# DJ_Controller_Circuit.net
KiCad netlist of a schematic drawn in EasyEDA Pro
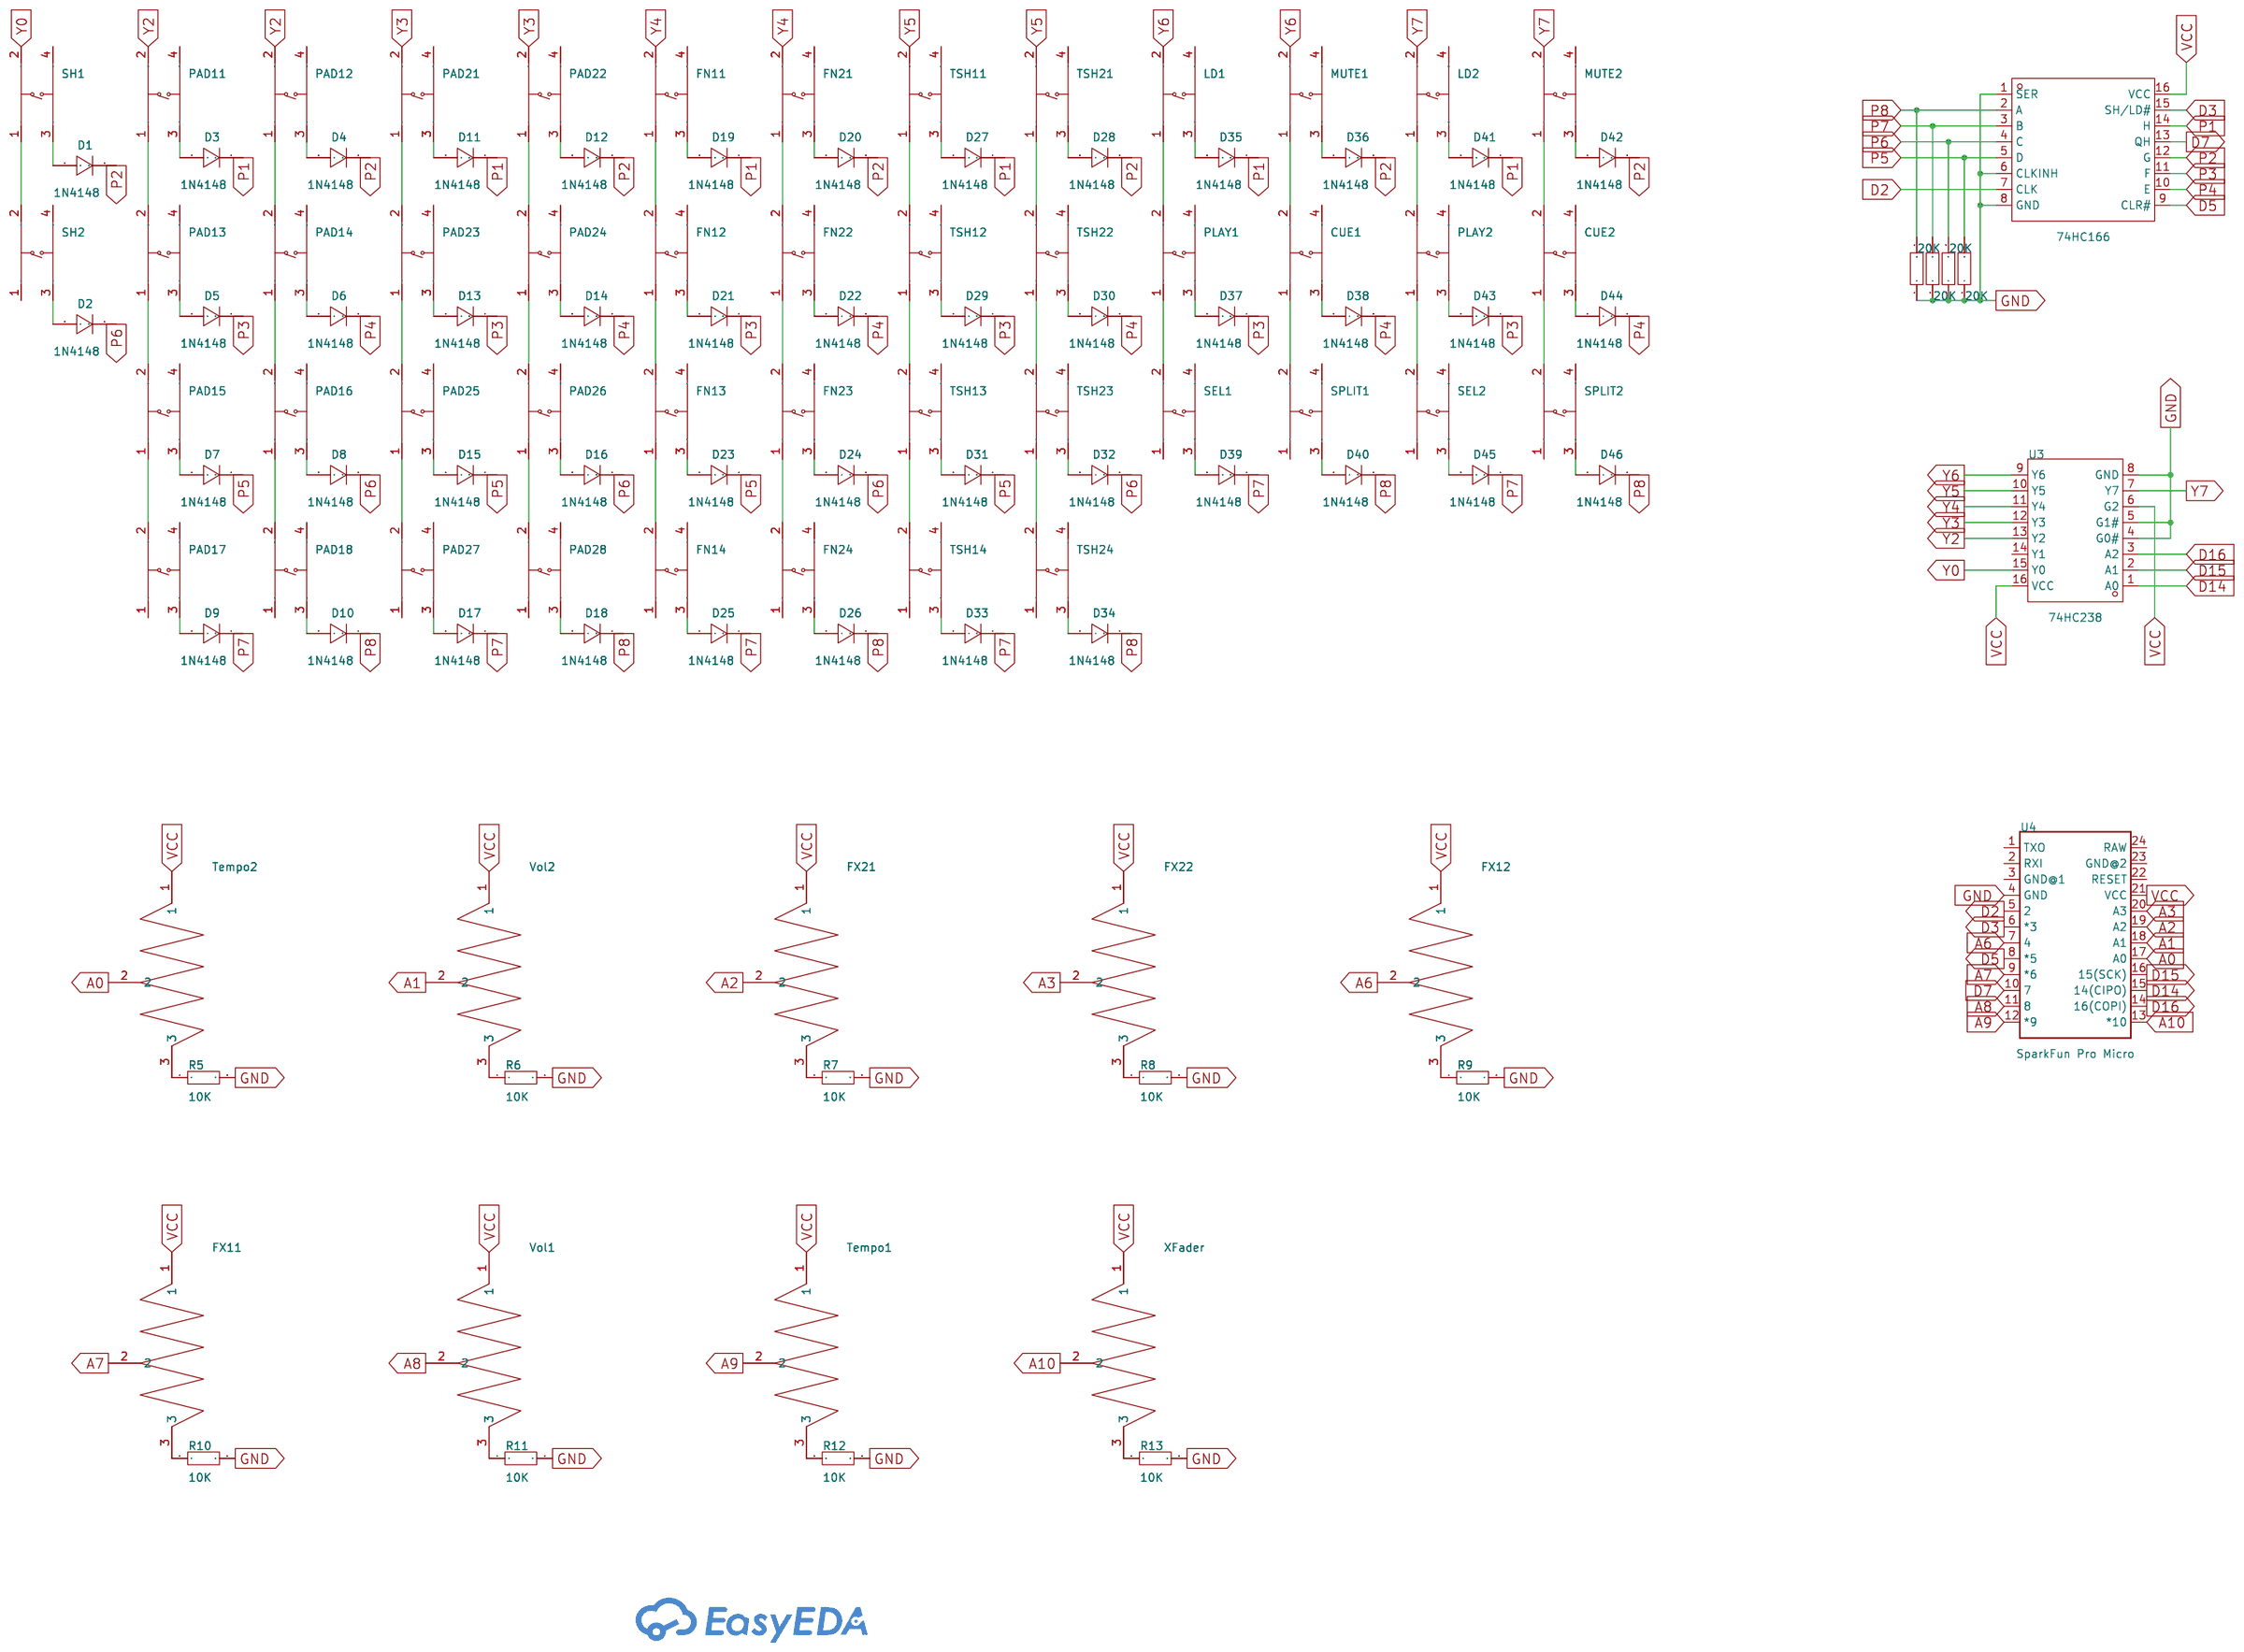
[diagram p0: schematic sheet]

(export (version "E")
  (design (tool "Eeschema 10.0.6"))
  (components
    (comp (ref "CUE1")
      (value "TS665CJ")
      (footprint "easyedapro:SW-TH_4P-L6.0-W6.0-P4.50-LS6.5")
      (fields (field (name "Manufacturer") "SHOU HAN(首韩)"))
      (libsource (lib "easyedapro") (part "TS665CJ"))
    )
    (comp (ref "CUE2")
      (value "TS665CJ")
      (footprint "easyedapro:SW-TH_4P-L6.0-W6.0-P4.50-LS6.5")
      (fields (field (name "Manufacturer") "SHOU HAN(首韩)"))
      (libsource (lib "easyedapro") (part "TS665CJ"))
    )
    (comp (ref "D1")
      (value "1N4148")
      (footprint "easyedapro:DO-35_BD2.0-L4.2-P8.20-D0.5-RD")
      (fields (field (name "Manufacturer") "星海"))
      (libsource (lib "easyedapro") (part "1N4148-C85057"))
    )
    (comp (ref "D2")
      (value "1N4148")
      (footprint "easyedapro:DO-35_BD2.0-L4.2-P8.20-D0.5-RD")
      (fields (field (name "Manufacturer") "星海"))
      (libsource (lib "easyedapro") (part "1N4148-C85057"))
    )
    (comp (ref "D3")
      (value "1N4148")
      (footprint "easyedapro:DO-35_BD2.0-L4.2-P8.20-D0.5-RD")
      (fields (field (name "Manufacturer") "星海"))
      (libsource (lib "easyedapro") (part "1N4148-C85057"))
    )
    (comp (ref "D4")
      (value "1N4148")
      (footprint "easyedapro:DO-35_BD2.0-L4.2-P8.20-D0.5-RD")
      (fields (field (name "Manufacturer") "星海"))
      (libsource (lib "easyedapro") (part "1N4148-C85057"))
    )
    (comp (ref "D5")
      (value "1N4148")
      (footprint "easyedapro:DO-35_BD2.0-L4.2-P8.20-D0.5-RD")
      (fields (field (name "Manufacturer") "星海"))
      (libsource (lib "easyedapro") (part "1N4148-C85057"))
    )
    (comp (ref "D6")
      (value "1N4148")
      (footprint "easyedapro:DO-35_BD2.0-L4.2-P8.20-D0.5-RD")
      (fields (field (name "Manufacturer") "星海"))
      (libsource (lib "easyedapro") (part "1N4148-C85057"))
    )
    (comp (ref "D7")
      (value "1N4148")
      (footprint "easyedapro:DO-35_BD2.0-L4.2-P8.20-D0.5-RD")
      (fields (field (name "Manufacturer") "星海"))
      (libsource (lib "easyedapro") (part "1N4148-C85057"))
    )
    (comp (ref "D8")
      (value "1N4148")
      (footprint "easyedapro:DO-35_BD2.0-L4.2-P8.20-D0.5-RD")
      (fields (field (name "Manufacturer") "星海"))
      (libsource (lib "easyedapro") (part "1N4148-C85057"))
    )
    (comp (ref "D9")
      (value "1N4148")
      (footprint "easyedapro:DO-35_BD2.0-L4.2-P8.20-D0.5-RD")
      (fields (field (name "Manufacturer") "星海"))
      (libsource (lib "easyedapro") (part "1N4148-C85057"))
    )
    (comp (ref "D10")
      (value "1N4148")
      (footprint "easyedapro:DO-35_BD2.0-L4.2-P8.20-D0.5-RD")
      (fields (field (name "Manufacturer") "星海"))
      (libsource (lib "easyedapro") (part "1N4148-C85057"))
    )
    (comp (ref "D11")
      (value "1N4148")
      (footprint "easyedapro:DO-35_BD2.0-L4.2-P8.20-D0.5-RD")
      (fields (field (name "Manufacturer") "星海"))
      (libsource (lib "easyedapro") (part "1N4148-C85057"))
    )
    (comp (ref "D12")
      (value "1N4148")
      (footprint "easyedapro:DO-35_BD2.0-L4.2-P8.20-D0.5-RD")
      (fields (field (name "Manufacturer") "星海"))
      (libsource (lib "easyedapro") (part "1N4148-C85057"))
    )
    (comp (ref "D13")
      (value "1N4148")
      (footprint "easyedapro:DO-35_BD2.0-L4.2-P8.20-D0.5-RD")
      (fields (field (name "Manufacturer") "星海"))
      (libsource (lib "easyedapro") (part "1N4148-C85057"))
    )
    (comp (ref "D14")
      (value "1N4148")
      (footprint "easyedapro:DO-35_BD2.0-L4.2-P8.20-D0.5-RD")
      (fields (field (name "Manufacturer") "星海"))
      (libsource (lib "easyedapro") (part "1N4148-C85057"))
    )
    (comp (ref "D15")
      (value "1N4148")
      (footprint "easyedapro:DO-35_BD2.0-L4.2-P8.20-D0.5-RD")
      (fields (field (name "Manufacturer") "星海"))
      (libsource (lib "easyedapro") (part "1N4148-C85057"))
    )
    (comp (ref "D16")
      (value "1N4148")
      (footprint "easyedapro:DO-35_BD2.0-L4.2-P8.20-D0.5-RD")
      (fields (field (name "Manufacturer") "星海"))
      (libsource (lib "easyedapro") (part "1N4148-C85057"))
    )
    (comp (ref "D17")
      (value "1N4148")
      (footprint "easyedapro:DO-35_BD2.0-L4.2-P8.20-D0.5-RD")
      (fields (field (name "Manufacturer") "星海"))
      (libsource (lib "easyedapro") (part "1N4148-C85057"))
    )
    (comp (ref "D18")
      (value "1N4148")
      (footprint "easyedapro:DO-35_BD2.0-L4.2-P8.20-D0.5-RD")
      (fields (field (name "Manufacturer") "星海"))
      (libsource (lib "easyedapro") (part "1N4148-C85057"))
    )
    (comp (ref "D19")
      (value "1N4148")
      (footprint "easyedapro:DO-35_BD2.0-L4.2-P8.20-D0.5-RD")
      (fields (field (name "Manufacturer") "星海"))
      (libsource (lib "easyedapro") (part "1N4148-C85057"))
    )
    (comp (ref "D20")
      (value "1N4148")
      (footprint "easyedapro:DO-35_BD2.0-L4.2-P8.20-D0.5-RD")
      (fields (field (name "Manufacturer") "星海"))
      (libsource (lib "easyedapro") (part "1N4148-C85057"))
    )
    (comp (ref "D21")
      (value "1N4148")
      (footprint "easyedapro:DO-35_BD2.0-L4.2-P8.20-D0.5-RD")
      (fields (field (name "Manufacturer") "星海"))
      (libsource (lib "easyedapro") (part "1N4148-C85057"))
    )
    (comp (ref "D22")
      (value "1N4148")
      (footprint "easyedapro:DO-35_BD2.0-L4.2-P8.20-D0.5-RD")
      (fields (field (name "Manufacturer") "星海"))
      (libsource (lib "easyedapro") (part "1N4148-C85057"))
    )
    (comp (ref "D23")
      (value "1N4148")
      (footprint "easyedapro:DO-35_BD2.0-L4.2-P8.20-D0.5-RD")
      (fields (field (name "Manufacturer") "星海"))
      (libsource (lib "easyedapro") (part "1N4148-C85057"))
    )
    (comp (ref "D24")
      (value "1N4148")
      (footprint "easyedapro:DO-35_BD2.0-L4.2-P8.20-D0.5-RD")
      (fields (field (name "Manufacturer") "星海"))
      (libsource (lib "easyedapro") (part "1N4148-C85057"))
    )
    (comp (ref "D25")
      (value "1N4148")
      (footprint "easyedapro:DO-35_BD2.0-L4.2-P8.20-D0.5-RD")
      (fields (field (name "Manufacturer") "星海"))
      (libsource (lib "easyedapro") (part "1N4148-C85057"))
    )
    (comp (ref "D26")
      (value "1N4148")
      (footprint "easyedapro:DO-35_BD2.0-L4.2-P8.20-D0.5-RD")
      (fields (field (name "Manufacturer") "星海"))
      (libsource (lib "easyedapro") (part "1N4148-C85057"))
    )
    (comp (ref "D27")
      (value "1N4148")
      (footprint "easyedapro:DO-35_BD2.0-L4.2-P8.20-D0.5-RD")
      (fields (field (name "Manufacturer") "星海"))
      (libsource (lib "easyedapro") (part "1N4148-C85057"))
    )
    (comp (ref "D28")
      (value "1N4148")
      (footprint "easyedapro:DO-35_BD2.0-L4.2-P8.20-D0.5-RD")
      (fields (field (name "Manufacturer") "星海"))
      (libsource (lib "easyedapro") (part "1N4148-C85057"))
    )
    (comp (ref "D29")
      (value "1N4148")
      (footprint "easyedapro:DO-35_BD2.0-L4.2-P8.20-D0.5-RD")
      (fields (field (name "Manufacturer") "星海"))
      (libsource (lib "easyedapro") (part "1N4148-C85057"))
    )
    (comp (ref "D30")
      (value "1N4148")
      (footprint "easyedapro:DO-35_BD2.0-L4.2-P8.20-D0.5-RD")
      (fields (field (name "Manufacturer") "星海"))
      (libsource (lib "easyedapro") (part "1N4148-C85057"))
    )
    (comp (ref "D31")
      (value "1N4148")
      (footprint "easyedapro:DO-35_BD2.0-L4.2-P8.20-D0.5-RD")
      (fields (field (name "Manufacturer") "星海"))
      (libsource (lib "easyedapro") (part "1N4148-C85057"))
    )
    (comp (ref "D32")
      (value "1N4148")
      (footprint "easyedapro:DO-35_BD2.0-L4.2-P8.20-D0.5-RD")
      (fields (field (name "Manufacturer") "星海"))
      (libsource (lib "easyedapro") (part "1N4148-C85057"))
    )
    (comp (ref "D33")
      (value "1N4148")
      (footprint "easyedapro:DO-35_BD2.0-L4.2-P8.20-D0.5-RD")
      (fields (field (name "Manufacturer") "星海"))
      (libsource (lib "easyedapro") (part "1N4148-C85057"))
    )
    (comp (ref "D34")
      (value "1N4148")
      (footprint "easyedapro:DO-35_BD2.0-L4.2-P8.20-D0.5-RD")
      (fields (field (name "Manufacturer") "星海"))
      (libsource (lib "easyedapro") (part "1N4148-C85057"))
    )
    (comp (ref "D35")
      (value "1N4148")
      (footprint "easyedapro:DO-35_BD2.0-L4.2-P8.20-D0.5-RD")
      (fields (field (name "Manufacturer") "星海"))
      (libsource (lib "easyedapro") (part "1N4148-C85057"))
    )
    (comp (ref "D36")
      (value "1N4148")
      (footprint "easyedapro:DO-35_BD2.0-L4.2-P8.20-D0.5-RD")
      (fields (field (name "Manufacturer") "星海"))
      (libsource (lib "easyedapro") (part "1N4148-C85057"))
    )
    (comp (ref "D37")
      (value "1N4148")
      (footprint "easyedapro:DO-35_BD2.0-L4.2-P8.20-D0.5-RD")
      (fields (field (name "Manufacturer") "星海"))
      (libsource (lib "easyedapro") (part "1N4148-C85057"))
    )
    (comp (ref "D38")
      (value "1N4148")
      (footprint "easyedapro:DO-35_BD2.0-L4.2-P8.20-D0.5-RD")
      (fields (field (name "Manufacturer") "星海"))
      (libsource (lib "easyedapro") (part "1N4148-C85057"))
    )
    (comp (ref "D39")
      (value "1N4148")
      (footprint "easyedapro:DO-35_BD2.0-L4.2-P8.20-D0.5-RD")
      (fields (field (name "Manufacturer") "星海"))
      (libsource (lib "easyedapro") (part "1N4148-C85057"))
    )
    (comp (ref "D40")
      (value "1N4148")
      (footprint "easyedapro:DO-35_BD2.0-L4.2-P8.20-D0.5-RD")
      (fields (field (name "Manufacturer") "星海"))
      (libsource (lib "easyedapro") (part "1N4148-C85057"))
    )
    (comp (ref "D41")
      (value "1N4148")
      (footprint "easyedapro:DO-35_BD2.0-L4.2-P8.20-D0.5-RD")
      (fields (field (name "Manufacturer") "星海"))
      (libsource (lib "easyedapro") (part "1N4148-C85057"))
    )
    (comp (ref "D42")
      (value "1N4148")
      (footprint "easyedapro:DO-35_BD2.0-L4.2-P8.20-D0.5-RD")
      (fields (field (name "Manufacturer") "星海"))
      (libsource (lib "easyedapro") (part "1N4148-C85057"))
    )
    (comp (ref "D43")
      (value "1N4148")
      (footprint "easyedapro:DO-35_BD2.0-L4.2-P8.20-D0.5-RD")
      (fields (field (name "Manufacturer") "星海"))
      (libsource (lib "easyedapro") (part "1N4148-C85057"))
    )
    (comp (ref "D44")
      (value "1N4148")
      (footprint "easyedapro:DO-35_BD2.0-L4.2-P8.20-D0.5-RD")
      (fields (field (name "Manufacturer") "星海"))
      (libsource (lib "easyedapro") (part "1N4148-C85057"))
    )
    (comp (ref "D45")
      (value "1N4148")
      (footprint "easyedapro:DO-35_BD2.0-L4.2-P8.20-D0.5-RD")
      (fields (field (name "Manufacturer") "星海"))
      (libsource (lib "easyedapro") (part "1N4148-C85057"))
    )
    (comp (ref "D46")
      (value "1N4148")
      (footprint "easyedapro:DO-35_BD2.0-L4.2-P8.20-D0.5-RD")
      (fields (field (name "Manufacturer") "星海"))
      (libsource (lib "easyedapro") (part "1N4148-C85057"))
    )
    (comp (ref "FN11")
      (value "TS665CJ")
      (footprint "easyedapro:SW-TH_4P-L6.0-W6.0-P4.50-LS6.5")
      (fields (field (name "Manufacturer") "SHOU HAN(首韩)"))
      (libsource (lib "easyedapro") (part "TS665CJ"))
    )
    (comp (ref "FN12")
      (value "TS665CJ")
      (footprint "easyedapro:SW-TH_4P-L6.0-W6.0-P4.50-LS6.5")
      (fields (field (name "Manufacturer") "SHOU HAN(首韩)"))
      (libsource (lib "easyedapro") (part "TS665CJ"))
    )
    (comp (ref "FN13")
      (value "TS665CJ")
      (footprint "easyedapro:SW-TH_4P-L6.0-W6.0-P4.50-LS6.5")
      (fields (field (name "Manufacturer") "SHOU HAN(首韩)"))
      (libsource (lib "easyedapro") (part "TS665CJ"))
    )
    (comp (ref "FN14")
      (value "TS665CJ")
      (footprint "easyedapro:SW-TH_4P-L6.0-W6.0-P4.50-LS6.5")
      (fields (field (name "Manufacturer") "SHOU HAN(首韩)"))
      (libsource (lib "easyedapro") (part "TS665CJ"))
    )
    (comp (ref "FN21")
      (value "TS665CJ")
      (footprint "easyedapro:SW-TH_4P-L6.0-W6.0-P4.50-LS6.5")
      (fields (field (name "Manufacturer") "SHOU HAN(首韩)"))
      (libsource (lib "easyedapro") (part "TS665CJ"))
    )
    (comp (ref "FN22")
      (value "TS665CJ")
      (footprint "easyedapro:SW-TH_4P-L6.0-W6.0-P4.50-LS6.5")
      (fields (field (name "Manufacturer") "SHOU HAN(首韩)"))
      (libsource (lib "easyedapro") (part "TS665CJ"))
    )
    (comp (ref "FN23")
      (value "TS665CJ")
      (footprint "easyedapro:SW-TH_4P-L6.0-W6.0-P4.50-LS6.5")
      (fields (field (name "Manufacturer") "SHOU HAN(首韩)"))
      (libsource (lib "easyedapro") (part "TS665CJ"))
    )
    (comp (ref "FN24")
      (value "TS665CJ")
      (footprint "easyedapro:SW-TH_4P-L6.0-W6.0-P4.50-LS6.5")
      (fields (field (name "Manufacturer") "SHOU HAN(首韩)"))
      (libsource (lib "easyedapro") (part "TS665CJ"))
    )
    (comp (ref "FX11") (value "~") (libsource (lib "easyedapro") (part "DM4070")))
    (comp (ref "FX12") (value "~") (libsource (lib "easyedapro") (part "DM4070")))
    (comp (ref "FX21") (value "~") (libsource (lib "easyedapro") (part "DM4070")))
    (comp (ref "FX22") (value "~") (libsource (lib "easyedapro") (part "DM4070")))
    (comp (ref "LD1")
      (value "TS665CJ")
      (footprint "easyedapro:SW-TH_4P-L6.0-W6.0-P4.50-LS6.5")
      (fields (field (name "Manufacturer") "SHOU HAN(首韩)"))
      (libsource (lib "easyedapro") (part "TS665CJ"))
    )
    (comp (ref "LD2")
      (value "TS665CJ")
      (footprint "easyedapro:SW-TH_4P-L6.0-W6.0-P4.50-LS6.5")
      (fields (field (name "Manufacturer") "SHOU HAN(首韩)"))
      (libsource (lib "easyedapro") (part "TS665CJ"))
    )
    (comp (ref "MUTE1")
      (value "TS665CJ")
      (footprint "easyedapro:SW-TH_4P-L6.0-W6.0-P4.50-LS6.5")
      (fields (field (name "Manufacturer") "SHOU HAN(首韩)"))
      (libsource (lib "easyedapro") (part "TS665CJ"))
    )
    (comp (ref "MUTE2")
      (value "TS665CJ")
      (footprint "easyedapro:SW-TH_4P-L6.0-W6.0-P4.50-LS6.5")
      (fields (field (name "Manufacturer") "SHOU HAN(首韩)"))
      (libsource (lib "easyedapro") (part "TS665CJ"))
    )
    (comp (ref "PAD11")
      (value "TS665CJ")
      (footprint "easyedapro:SW-TH_4P-L6.0-W6.0-P4.50-LS6.5")
      (fields (field (name "Manufacturer") "SHOU HAN(首韩)"))
      (libsource (lib "easyedapro") (part "TS665CJ"))
    )
    (comp (ref "PAD12")
      (value "TS665CJ")
      (footprint "easyedapro:SW-TH_4P-L6.0-W6.0-P4.50-LS6.5")
      (fields (field (name "Manufacturer") "SHOU HAN(首韩)"))
      (libsource (lib "easyedapro") (part "TS665CJ"))
    )
    (comp (ref "PAD13")
      (value "TS665CJ")
      (footprint "easyedapro:SW-TH_4P-L6.0-W6.0-P4.50-LS6.5")
      (fields (field (name "Manufacturer") "SHOU HAN(首韩)"))
      (libsource (lib "easyedapro") (part "TS665CJ"))
    )
    (comp (ref "PAD14")
      (value "TS665CJ")
      (footprint "easyedapro:SW-TH_4P-L6.0-W6.0-P4.50-LS6.5")
      (fields (field (name "Manufacturer") "SHOU HAN(首韩)"))
      (libsource (lib "easyedapro") (part "TS665CJ"))
    )
    (comp (ref "PAD15")
      (value "TS665CJ")
      (footprint "easyedapro:SW-TH_4P-L6.0-W6.0-P4.50-LS6.5")
      (fields (field (name "Manufacturer") "SHOU HAN(首韩)"))
      (libsource (lib "easyedapro") (part "TS665CJ"))
    )
    (comp (ref "PAD16")
      (value "TS665CJ")
      (footprint "easyedapro:SW-TH_4P-L6.0-W6.0-P4.50-LS6.5")
      (fields (field (name "Manufacturer") "SHOU HAN(首韩)"))
      (libsource (lib "easyedapro") (part "TS665CJ"))
    )
    (comp (ref "PAD17")
      (value "TS665CJ")
      (footprint "easyedapro:SW-TH_4P-L6.0-W6.0-P4.50-LS6.5")
      (fields (field (name "Manufacturer") "SHOU HAN(首韩)"))
      (libsource (lib "easyedapro") (part "TS665CJ"))
    )
    (comp (ref "PAD18")
      (value "TS665CJ")
      (footprint "easyedapro:SW-TH_4P-L6.0-W6.0-P4.50-LS6.5")
      (fields (field (name "Manufacturer") "SHOU HAN(首韩)"))
      (libsource (lib "easyedapro") (part "TS665CJ"))
    )
    (comp (ref "PAD21")
      (value "TS665CJ")
      (footprint "easyedapro:SW-TH_4P-L6.0-W6.0-P4.50-LS6.5")
      (fields (field (name "Manufacturer") "SHOU HAN(首韩)"))
      (libsource (lib "easyedapro") (part "TS665CJ"))
    )
    (comp (ref "PAD22")
      (value "TS665CJ")
      (footprint "easyedapro:SW-TH_4P-L6.0-W6.0-P4.50-LS6.5")
      (fields (field (name "Manufacturer") "SHOU HAN(首韩)"))
      (libsource (lib "easyedapro") (part "TS665CJ"))
    )
    (comp (ref "PAD23")
      (value "TS665CJ")
      (footprint "easyedapro:SW-TH_4P-L6.0-W6.0-P4.50-LS6.5")
      (fields (field (name "Manufacturer") "SHOU HAN(首韩)"))
      (libsource (lib "easyedapro") (part "TS665CJ"))
    )
    (comp (ref "PAD24")
      (value "TS665CJ")
      (footprint "easyedapro:SW-TH_4P-L6.0-W6.0-P4.50-LS6.5")
      (fields (field (name "Manufacturer") "SHOU HAN(首韩)"))
      (libsource (lib "easyedapro") (part "TS665CJ"))
    )
    (comp (ref "PAD25")
      (value "TS665CJ")
      (footprint "easyedapro:SW-TH_4P-L6.0-W6.0-P4.50-LS6.5")
      (fields (field (name "Manufacturer") "SHOU HAN(首韩)"))
      (libsource (lib "easyedapro") (part "TS665CJ"))
    )
    (comp (ref "PAD26")
      (value "TS665CJ")
      (footprint "easyedapro:SW-TH_4P-L6.0-W6.0-P4.50-LS6.5")
      (fields (field (name "Manufacturer") "SHOU HAN(首韩)"))
      (libsource (lib "easyedapro") (part "TS665CJ"))
    )
    (comp (ref "PAD27")
      (value "TS665CJ")
      (footprint "easyedapro:SW-TH_4P-L6.0-W6.0-P4.50-LS6.5")
      (fields (field (name "Manufacturer") "SHOU HAN(首韩)"))
      (libsource (lib "easyedapro") (part "TS665CJ"))
    )
    (comp (ref "PAD28")
      (value "TS665CJ")
      (footprint "easyedapro:SW-TH_4P-L6.0-W6.0-P4.50-LS6.5")
      (fields (field (name "Manufacturer") "SHOU HAN(首韩)"))
      (libsource (lib "easyedapro") (part "TS665CJ"))
    )
    (comp (ref "PLAY1")
      (value "TS665CJ")
      (footprint "easyedapro:SW-TH_4P-L6.0-W6.0-P4.50-LS6.5")
      (fields (field (name "Manufacturer") "SHOU HAN(首韩)"))
      (libsource (lib "easyedapro") (part "TS665CJ"))
    )
    (comp (ref "PLAY2")
      (value "TS665CJ")
      (footprint "easyedapro:SW-TH_4P-L6.0-W6.0-P4.50-LS6.5")
      (fields (field (name "Manufacturer") "SHOU HAN(首韩)"))
      (libsource (lib "easyedapro") (part "TS665CJ"))
    )
    (comp (ref "R1") (value "20K") (footprint "easyedapro:R0603") (libsource (lib "easyedapro") (part "Res")))
    (comp (ref "R2") (value "20K") (footprint "easyedapro:R0603") (libsource (lib "easyedapro") (part "Res")))
    (comp (ref "R3") (value "20K") (footprint "easyedapro:R0603") (libsource (lib "easyedapro") (part "Res")))
    (comp (ref "R4") (value "20K") (footprint "easyedapro:R0603") (libsource (lib "easyedapro") (part "Res")))
    (comp (ref "R5") (value "10K") (footprint "easyedapro:R0603") (libsource (lib "easyedapro") (part "Res")))
    (comp (ref "R6") (value "10K") (footprint "easyedapro:R0603") (libsource (lib "easyedapro") (part "Res")))
    (comp (ref "R7") (value "10K") (footprint "easyedapro:R0603") (libsource (lib "easyedapro") (part "Res")))
    (comp (ref "R8") (value "10K") (footprint "easyedapro:R0603") (libsource (lib "easyedapro") (part "Res")))
    (comp (ref "R9") (value "10K") (footprint "easyedapro:R0603") (libsource (lib "easyedapro") (part "Res")))
    (comp (ref "R10")
      (value "10K")
      (footprint "easyedapro:R0603")
      (libsource (lib "easyedapro") (part "Res"))
    )
    (comp (ref "R11")
      (value "10K")
      (footprint "easyedapro:R0603")
      (libsource (lib "easyedapro") (part "Res"))
    )
    (comp (ref "R12")
      (value "10K")
      (footprint "easyedapro:R0603")
      (libsource (lib "easyedapro") (part "Res"))
    )
    (comp (ref "R13")
      (value "10K")
      (footprint "easyedapro:R0603")
      (libsource (lib "easyedapro") (part "Res"))
    )
    (comp (ref "SEL1")
      (value "TS665CJ")
      (footprint "easyedapro:SW-TH_4P-L6.0-W6.0-P4.50-LS6.5")
      (fields (field (name "Manufacturer") "SHOU HAN(首韩)"))
      (libsource (lib "easyedapro") (part "TS665CJ"))
    )
    (comp (ref "SEL2")
      (value "TS665CJ")
      (footprint "easyedapro:SW-TH_4P-L6.0-W6.0-P4.50-LS6.5")
      (fields (field (name "Manufacturer") "SHOU HAN(首韩)"))
      (libsource (lib "easyedapro") (part "TS665CJ"))
    )
    (comp (ref "SH1")
      (value "TS665CJ")
      (footprint "easyedapro:SW-TH_4P-L6.0-W6.0-P4.50-LS6.5")
      (fields (field (name "Manufacturer") "SHOU HAN(首韩)"))
      (libsource (lib "easyedapro") (part "TS665CJ"))
    )
    (comp (ref "SH2")
      (value "TS665CJ")
      (footprint "easyedapro:SW-TH_4P-L6.0-W6.0-P4.50-LS6.5")
      (fields (field (name "Manufacturer") "SHOU HAN(首韩)"))
      (libsource (lib "easyedapro") (part "TS665CJ"))
    )
    (comp (ref "SPLIT1")
      (value "TS665CJ")
      (footprint "easyedapro:SW-TH_4P-L6.0-W6.0-P4.50-LS6.5")
      (fields (field (name "Manufacturer") "SHOU HAN(首韩)"))
      (libsource (lib "easyedapro") (part "TS665CJ"))
    )
    (comp (ref "SPLIT2")
      (value "TS665CJ")
      (footprint "easyedapro:SW-TH_4P-L6.0-W6.0-P4.50-LS6.5")
      (fields (field (name "Manufacturer") "SHOU HAN(首韩)"))
      (libsource (lib "easyedapro") (part "TS665CJ"))
    )
    (comp (ref "Tempo1") (value "~") (libsource (lib "easyedapro") (part "DM4070")))
    (comp (ref "Tempo2") (value "~") (libsource (lib "easyedapro") (part "DM4070")))
    (comp (ref "TSH11")
      (value "TS665CJ")
      (footprint "easyedapro:SW-TH_4P-L6.0-W6.0-P4.50-LS6.5")
      (fields (field (name "Manufacturer") "SHOU HAN(首韩)"))
      (libsource (lib "easyedapro") (part "TS665CJ"))
    )
    (comp (ref "TSH12")
      (value "TS665CJ")
      (footprint "easyedapro:SW-TH_4P-L6.0-W6.0-P4.50-LS6.5")
      (fields (field (name "Manufacturer") "SHOU HAN(首韩)"))
      (libsource (lib "easyedapro") (part "TS665CJ"))
    )
    (comp (ref "TSH13")
      (value "TS665CJ")
      (footprint "easyedapro:SW-TH_4P-L6.0-W6.0-P4.50-LS6.5")
      (fields (field (name "Manufacturer") "SHOU HAN(首韩)"))
      (libsource (lib "easyedapro") (part "TS665CJ"))
    )
    (comp (ref "TSH14")
      (value "TS665CJ")
      (footprint "easyedapro:SW-TH_4P-L6.0-W6.0-P4.50-LS6.5")
      (fields (field (name "Manufacturer") "SHOU HAN(首韩)"))
      (libsource (lib "easyedapro") (part "TS665CJ"))
    )
    (comp (ref "TSH21")
      (value "TS665CJ")
      (footprint "easyedapro:SW-TH_4P-L6.0-W6.0-P4.50-LS6.5")
      (fields (field (name "Manufacturer") "SHOU HAN(首韩)"))
      (libsource (lib "easyedapro") (part "TS665CJ"))
    )
    (comp (ref "TSH22")
      (value "TS665CJ")
      (footprint "easyedapro:SW-TH_4P-L6.0-W6.0-P4.50-LS6.5")
      (fields (field (name "Manufacturer") "SHOU HAN(首韩)"))
      (libsource (lib "easyedapro") (part "TS665CJ"))
    )
    (comp (ref "TSH23")
      (value "TS665CJ")
      (footprint "easyedapro:SW-TH_4P-L6.0-W6.0-P4.50-LS6.5")
      (fields (field (name "Manufacturer") "SHOU HAN(首韩)"))
      (libsource (lib "easyedapro") (part "TS665CJ"))
    )
    (comp (ref "TSH24")
      (value "TS665CJ")
      (footprint "easyedapro:SW-TH_4P-L6.0-W6.0-P4.50-LS6.5")
      (fields (field (name "Manufacturer") "SHOU HAN(首韩)"))
      (libsource (lib "easyedapro") (part "TS665CJ"))
    )
    (comp (ref "U2")
      (value "74HC166")
      (footprint "easyedapro:DIP-16_L20.0-W6.4-P2.54-LS7.6-BL")
      (fields (field (name "Manufacturer Part") "SN74HC166N") (field (name "Manufacturer") "TI(德州仪器)"))
      (libsource (lib "easyedapro") (part "SN74HC166N"))
    )
    (comp (ref "U3")
      (value "74HC238")
      (footprint "easyedapro:PDIP-16_L19.3-W6.4-P2.54-LS7.9-BL")
      (fields (field (name "Manufacturer Part") "CD74HC238E") (field (name "Manufacturer") "TI(德州仪器)"))
      (libsource (lib "easyedapro") (part "CD74HC238E"))
    )
    (comp (ref "U4")
      (value "SparkFun Pro Micro")
      (footprint "easyedapro:SPARKFUN_PRO_MICRO")
      (libsource (lib "easyedapro") (part "SPARKFUN_PRO_MICRO"))
    )
    (comp (ref "Vol1") (value "~") (libsource (lib "easyedapro") (part "DM4070")))
    (comp (ref "Vol2") (value "~") (libsource (lib "easyedapro") (part "DM4070")))
    (comp (ref "XFader") (value "~") (libsource (lib "easyedapro") (part "DM4070")))
  )
  (nets
    (net (code "1") (name "A0") (class "Default")
      (node (ref "Tempo2") (pin "2") (pinfunction "2_2") (pintype "input"))
      (node (ref "U4") (pin "17") (pinfunction "A0_17") (pintype "bidirectional"))
    )
    (net (code "2") (name "A1") (class "Default")
      (node (ref "U4") (pin "18") (pinfunction "A1_18") (pintype "bidirectional"))
      (node (ref "Vol2") (pin "2") (pinfunction "2_2") (pintype "input"))
    )
    (net (code "3") (name "A2") (class "Default")
      (node (ref "FX21") (pin "2") (pinfunction "2_2") (pintype "input"))
      (node (ref "U4") (pin "19") (pinfunction "A2_19") (pintype "bidirectional"))
    )
    (net (code "4") (name "A3") (class "Default")
      (node (ref "FX22") (pin "2") (pinfunction "2_2") (pintype "input"))
      (node (ref "U4") (pin "20") (pinfunction "A3_20") (pintype "bidirectional"))
    )
    (net (code "5") (name "A6") (class "Default")
      (node (ref "FX12") (pin "2") (pinfunction "2_2") (pintype "input"))
      (node (ref "U4") (pin "7") (pinfunction "4_7") (pintype "bidirectional"))
    )
    (net (code "6") (name "A7") (class "Default")
      (node (ref "FX11") (pin "2") (pinfunction "2_2") (pintype "input"))
      (node (ref "U4") (pin "9") (pinfunction "*6_9") (pintype "bidirectional"))
    )
    (net (code "7") (name "A8") (class "Default")
      (node (ref "U4") (pin "11") (pinfunction "8_11") (pintype "bidirectional"))
      (node (ref "Vol1") (pin "2") (pinfunction "2_2") (pintype "input"))
    )
    (net (code "8") (name "A9") (class "Default")
      (node (ref "Tempo1") (pin "2") (pinfunction "2_2") (pintype "input"))
      (node (ref "U4") (pin "12") (pinfunction "*9_12") (pintype "bidirectional"))
    )
    (net (code "9") (name "A10") (class "Default")
      (node (ref "U4") (pin "13") (pinfunction "*10_13") (pintype "bidirectional"))
      (node (ref "XFader") (pin "2") (pinfunction "2_2") (pintype "input"))
    )
    (net (code "10") (name "D2") (class "Default")
      (node (ref "U2") (pin "7") (pinfunction "CLK_7") (pintype "input"))
      (node (ref "U4") (pin "5") (pinfunction "2_5") (pintype "bidirectional"))
    )
    (net (code "11") (name "D3") (class "Default")
      (node (ref "U2") (pin "15") (pinfunction "SH/LD#_15") (pintype "input"))
      (node (ref "U4") (pin "6") (pinfunction "*3_6") (pintype "bidirectional"))
    )
    (net (code "12") (name "D5") (class "Default")
      (node (ref "U2") (pin "9") (pinfunction "CLR#_9") (pintype "input"))
      (node (ref "U4") (pin "8") (pinfunction "*5_8") (pintype "bidirectional"))
    )
    (net (code "13") (name "D7") (class "Default")
      (node (ref "U2") (pin "13") (pinfunction "QH_13") (pintype "input"))
      (node (ref "U4") (pin "10") (pinfunction "7_10") (pintype "bidirectional"))
    )
    (net (code "14") (name "D14") (class "Default")
      (node (ref "U3") (pin "1") (pinfunction "A0_1") (pintype "unspecified"))
      (node (ref "U4") (pin "15") (pinfunction "14(CIPO)_15") (pintype "bidirectional"))
    )
    (net (code "15") (name "D15") (class "Default")
      (node (ref "U3") (pin "2") (pinfunction "A1_2") (pintype "unspecified"))
      (node (ref "U4") (pin "16") (pinfunction "15(SCK)_16") (pintype "bidirectional"))
    )
    (net (code "16") (name "D16") (class "Default")
      (node (ref "U3") (pin "3") (pinfunction "A2_3") (pintype "unspecified"))
      (node (ref "U4") (pin "14") (pinfunction "16(COPI)_14") (pintype "bidirectional"))
    )
    (net (code "17") (name "GND") (class "Default")
      (node (ref "R1") (pin "1") (pinfunction "1_1") (pintype "input"))
      (node (ref "R10") (pin "2") (pinfunction "2_2") (pintype "input"))
      (node (ref "R11") (pin "2") (pinfunction "2_2") (pintype "input"))
      (node (ref "R12") (pin "2") (pinfunction "2_2") (pintype "input"))
      (node (ref "R13") (pin "2") (pinfunction "2_2") (pintype "input"))
      (node (ref "R2") (pin "1") (pinfunction "1_1") (pintype "input"))
      (node (ref "R3") (pin "1") (pinfunction "1_1") (pintype "input"))
      (node (ref "R4") (pin "1") (pinfunction "1_1") (pintype "input"))
      (node (ref "R5") (pin "2") (pinfunction "2_2") (pintype "input"))
      (node (ref "R6") (pin "2") (pinfunction "2_2") (pintype "input"))
      (node (ref "R7") (pin "2") (pinfunction "2_2") (pintype "input"))
      (node (ref "R8") (pin "2") (pinfunction "2_2") (pintype "input"))
      (node (ref "R9") (pin "2") (pinfunction "2_2") (pintype "input"))
      (node (ref "U2") (pin "1") (pinfunction "SER_1") (pintype "input"))
      (node (ref "U2") (pin "6") (pinfunction "CLKINH_6") (pintype "input"))
      (node (ref "U2") (pin "8") (pinfunction "GND_8") (pintype "input"))
      (node (ref "U3") (pin "4") (pinfunction "G0#_4") (pintype "unspecified"))
      (node (ref "U3") (pin "5") (pinfunction "G1#_5") (pintype "unspecified"))
      (node (ref "U3") (pin "8") (pinfunction "GND_8") (pintype "unspecified"))
      (node (ref "U4") (pin "4") (pinfunction "GND_4") (pintype "unspecified"))
    )
    (net (code "18") (name "Net-(CUE1-A)") (class "Default")
      (node (ref "CUE1") (pin "1") (pinfunction "A_1") (pintype "unspecified"))
      (node (ref "SPLIT1") (pin "2") (pinfunction "B_2") (pintype "unspecified"))
    )
    (net (code "19") (name "Net-(CUE1-B)") (class "Default")
      (node (ref "CUE1") (pin "2") (pinfunction "B_2") (pintype "unspecified"))
      (node (ref "MUTE1") (pin "1") (pinfunction "A_1") (pintype "unspecified"))
    )
    (net (code "20") (name "Net-(CUE1-C)") (class "Default")
      (node (ref "CUE1") (pin "3") (pinfunction "C_3") (pintype "unspecified"))
      (node (ref "D38") (pin "2") (pinfunction "A_2") (pintype "unspecified"))
    )
    (net (code "21") (name "Net-(CUE2-A)") (class "Default")
      (node (ref "CUE2") (pin "1") (pinfunction "A_1") (pintype "unspecified"))
      (node (ref "SPLIT2") (pin "2") (pinfunction "B_2") (pintype "unspecified"))
    )
    (net (code "22") (name "Net-(CUE2-B)") (class "Default")
      (node (ref "CUE2") (pin "2") (pinfunction "B_2") (pintype "unspecified"))
      (node (ref "MUTE2") (pin "1") (pinfunction "A_1") (pintype "unspecified"))
    )
    (net (code "23") (name "Net-(CUE2-C)") (class "Default")
      (node (ref "CUE2") (pin "3") (pinfunction "C_3") (pintype "unspecified"))
      (node (ref "D44") (pin "2") (pinfunction "A_2") (pintype "unspecified"))
    )
    (net (code "24") (name "Net-(D1-A)") (class "Default")
      (node (ref "D1") (pin "2") (pinfunction "A_2") (pintype "unspecified"))
      (node (ref "SH1") (pin "3") (pinfunction "C_3") (pintype "unspecified"))
    )
    (net (code "25") (name "Net-(D2-A)") (class "Default")
      (node (ref "D2") (pin "2") (pinfunction "A_2") (pintype "unspecified"))
      (node (ref "SH2") (pin "3") (pinfunction "C_3") (pintype "unspecified"))
    )
    (net (code "26") (name "Net-(D3-A)") (class "Default")
      (node (ref "D3") (pin "2") (pinfunction "A_2") (pintype "unspecified"))
      (node (ref "PAD11") (pin "3") (pinfunction "C_3") (pintype "unspecified"))
    )
    (net (code "27") (name "Net-(D4-A)") (class "Default")
      (node (ref "D4") (pin "2") (pinfunction "A_2") (pintype "unspecified"))
      (node (ref "PAD12") (pin "3") (pinfunction "C_3") (pintype "unspecified"))
    )
    (net (code "28") (name "Net-(D5-A)") (class "Default")
      (node (ref "D5") (pin "2") (pinfunction "A_2") (pintype "unspecified"))
      (node (ref "PAD13") (pin "3") (pinfunction "C_3") (pintype "unspecified"))
    )
    (net (code "29") (name "Net-(D6-A)") (class "Default")
      (node (ref "D6") (pin "2") (pinfunction "A_2") (pintype "unspecified"))
      (node (ref "PAD14") (pin "3") (pinfunction "C_3") (pintype "unspecified"))
    )
    (net (code "30") (name "Net-(D7-A)") (class "Default")
      (node (ref "D7") (pin "2") (pinfunction "A_2") (pintype "unspecified"))
      (node (ref "PAD15") (pin "3") (pinfunction "C_3") (pintype "unspecified"))
    )
    (net (code "31") (name "Net-(D8-A)") (class "Default")
      (node (ref "D8") (pin "2") (pinfunction "A_2") (pintype "unspecified"))
      (node (ref "PAD16") (pin "3") (pinfunction "C_3") (pintype "unspecified"))
    )
    (net (code "32") (name "Net-(D9-A)") (class "Default")
      (node (ref "D9") (pin "2") (pinfunction "A_2") (pintype "unspecified"))
      (node (ref "PAD17") (pin "3") (pinfunction "C_3") (pintype "unspecified"))
    )
    (net (code "33") (name "Net-(D10-A)") (class "Default")
      (node (ref "D10") (pin "2") (pinfunction "A_2") (pintype "unspecified"))
      (node (ref "PAD18") (pin "3") (pinfunction "C_3") (pintype "unspecified"))
    )
    (net (code "34") (name "Net-(D11-A)") (class "Default")
      (node (ref "D11") (pin "2") (pinfunction "A_2") (pintype "unspecified"))
      (node (ref "PAD21") (pin "3") (pinfunction "C_3") (pintype "unspecified"))
    )
    (net (code "35") (name "Net-(D12-A)") (class "Default")
      (node (ref "D12") (pin "2") (pinfunction "A_2") (pintype "unspecified"))
      (node (ref "PAD22") (pin "3") (pinfunction "C_3") (pintype "unspecified"))
    )
    (net (code "36") (name "Net-(D13-A)") (class "Default")
      (node (ref "D13") (pin "2") (pinfunction "A_2") (pintype "unspecified"))
      (node (ref "PAD23") (pin "3") (pinfunction "C_3") (pintype "unspecified"))
    )
    (net (code "37") (name "Net-(D14-A)") (class "Default")
      (node (ref "D14") (pin "2") (pinfunction "A_2") (pintype "unspecified"))
      (node (ref "PAD24") (pin "3") (pinfunction "C_3") (pintype "unspecified"))
    )
    (net (code "38") (name "Net-(D15-A)") (class "Default")
      (node (ref "D15") (pin "2") (pinfunction "A_2") (pintype "unspecified"))
      (node (ref "PAD25") (pin "3") (pinfunction "C_3") (pintype "unspecified"))
    )
    (net (code "39") (name "Net-(D16-A)") (class "Default")
      (node (ref "D16") (pin "2") (pinfunction "A_2") (pintype "unspecified"))
      (node (ref "PAD26") (pin "3") (pinfunction "C_3") (pintype "unspecified"))
    )
    (net (code "40") (name "Net-(D17-A)") (class "Default")
      (node (ref "D17") (pin "2") (pinfunction "A_2") (pintype "unspecified"))
      (node (ref "PAD27") (pin "3") (pinfunction "C_3") (pintype "unspecified"))
    )
    (net (code "41") (name "Net-(D18-A)") (class "Default")
      (node (ref "D18") (pin "2") (pinfunction "A_2") (pintype "unspecified"))
      (node (ref "PAD28") (pin "3") (pinfunction "C_3") (pintype "unspecified"))
    )
    (net (code "42") (name "Net-(D19-A)") (class "Default")
      (node (ref "D19") (pin "2") (pinfunction "A_2") (pintype "unspecified"))
      (node (ref "FN11") (pin "3") (pinfunction "C_3") (pintype "unspecified"))
    )
    (net (code "43") (name "Net-(D20-A)") (class "Default")
      (node (ref "D20") (pin "2") (pinfunction "A_2") (pintype "unspecified"))
      (node (ref "FN21") (pin "3") (pinfunction "C_3") (pintype "unspecified"))
    )
    (net (code "44") (name "Net-(D21-A)") (class "Default")
      (node (ref "D21") (pin "2") (pinfunction "A_2") (pintype "unspecified"))
      (node (ref "FN12") (pin "3") (pinfunction "C_3") (pintype "unspecified"))
    )
    (net (code "45") (name "Net-(D22-A)") (class "Default")
      (node (ref "D22") (pin "2") (pinfunction "A_2") (pintype "unspecified"))
      (node (ref "FN22") (pin "3") (pinfunction "C_3") (pintype "unspecified"))
    )
    (net (code "46") (name "Net-(D23-A)") (class "Default")
      (node (ref "D23") (pin "2") (pinfunction "A_2") (pintype "unspecified"))
      (node (ref "FN13") (pin "3") (pinfunction "C_3") (pintype "unspecified"))
    )
    (net (code "47") (name "Net-(D24-A)") (class "Default")
      (node (ref "D24") (pin "2") (pinfunction "A_2") (pintype "unspecified"))
      (node (ref "FN23") (pin "3") (pinfunction "C_3") (pintype "unspecified"))
    )
    (net (code "48") (name "Net-(D25-A)") (class "Default")
      (node (ref "D25") (pin "2") (pinfunction "A_2") (pintype "unspecified"))
      (node (ref "FN14") (pin "3") (pinfunction "C_3") (pintype "unspecified"))
    )
    (net (code "49") (name "Net-(D26-A)") (class "Default")
      (node (ref "D26") (pin "2") (pinfunction "A_2") (pintype "unspecified"))
      (node (ref "FN24") (pin "3") (pinfunction "C_3") (pintype "unspecified"))
    )
    (net (code "50") (name "Net-(D27-A)") (class "Default")
      (node (ref "D27") (pin "2") (pinfunction "A_2") (pintype "unspecified"))
      (node (ref "TSH11") (pin "3") (pinfunction "C_3") (pintype "unspecified"))
    )
    (net (code "51") (name "Net-(D28-A)") (class "Default")
      (node (ref "D28") (pin "2") (pinfunction "A_2") (pintype "unspecified"))
      (node (ref "TSH21") (pin "3") (pinfunction "C_3") (pintype "unspecified"))
    )
    (net (code "52") (name "Net-(D29-A)") (class "Default")
      (node (ref "D29") (pin "2") (pinfunction "A_2") (pintype "unspecified"))
      (node (ref "TSH12") (pin "3") (pinfunction "C_3") (pintype "unspecified"))
    )
    (net (code "53") (name "Net-(D30-A)") (class "Default")
      (node (ref "D30") (pin "2") (pinfunction "A_2") (pintype "unspecified"))
      (node (ref "TSH22") (pin "3") (pinfunction "C_3") (pintype "unspecified"))
    )
    (net (code "54") (name "Net-(D31-A)") (class "Default")
      (node (ref "D31") (pin "2") (pinfunction "A_2") (pintype "unspecified"))
      (node (ref "TSH13") (pin "3") (pinfunction "C_3") (pintype "unspecified"))
    )
    (net (code "55") (name "Net-(D32-A)") (class "Default")
      (node (ref "D32") (pin "2") (pinfunction "A_2") (pintype "unspecified"))
      (node (ref "TSH23") (pin "3") (pinfunction "C_3") (pintype "unspecified"))
    )
    (net (code "56") (name "Net-(D33-A)") (class "Default")
      (node (ref "D33") (pin "2") (pinfunction "A_2") (pintype "unspecified"))
      (node (ref "TSH14") (pin "3") (pinfunction "C_3") (pintype "unspecified"))
    )
    (net (code "57") (name "Net-(D34-A)") (class "Default")
      (node (ref "D34") (pin "2") (pinfunction "A_2") (pintype "unspecified"))
      (node (ref "TSH24") (pin "3") (pinfunction "C_3") (pintype "unspecified"))
    )
    (net (code "58") (name "Net-(D35-A)") (class "Default")
      (node (ref "D35") (pin "2") (pinfunction "A_2") (pintype "unspecified"))
      (node (ref "LD1") (pin "3") (pinfunction "C_3") (pintype "unspecified"))
    )
    (net (code "59") (name "Net-(D36-A)") (class "Default")
      (node (ref "D36") (pin "2") (pinfunction "A_2") (pintype "unspecified"))
      (node (ref "MUTE1") (pin "3") (pinfunction "C_3") (pintype "unspecified"))
    )
    (net (code "60") (name "Net-(D37-A)") (class "Default")
      (node (ref "D37") (pin "2") (pinfunction "A_2") (pintype "unspecified"))
      (node (ref "PLAY1") (pin "3") (pinfunction "C_3") (pintype "unspecified"))
    )
    (net (code "61") (name "Net-(D39-A)") (class "Default")
      (node (ref "D39") (pin "2") (pinfunction "A_2") (pintype "unspecified"))
      (node (ref "SEL1") (pin "3") (pinfunction "C_3") (pintype "unspecified"))
    )
    (net (code "62") (name "Net-(D40-A)") (class "Default")
      (node (ref "D40") (pin "2") (pinfunction "A_2") (pintype "unspecified"))
      (node (ref "SPLIT1") (pin "3") (pinfunction "C_3") (pintype "unspecified"))
    )
    (net (code "63") (name "Net-(D41-A)") (class "Default")
      (node (ref "D41") (pin "2") (pinfunction "A_2") (pintype "unspecified"))
      (node (ref "LD2") (pin "3") (pinfunction "C_3") (pintype "unspecified"))
    )
    (net (code "64") (name "Net-(D42-A)") (class "Default")
      (node (ref "D42") (pin "2") (pinfunction "A_2") (pintype "unspecified"))
      (node (ref "MUTE2") (pin "3") (pinfunction "C_3") (pintype "unspecified"))
    )
    (net (code "65") (name "Net-(D43-A)") (class "Default")
      (node (ref "D43") (pin "2") (pinfunction "A_2") (pintype "unspecified"))
      (node (ref "PLAY2") (pin "3") (pinfunction "C_3") (pintype "unspecified"))
    )
    (net (code "66") (name "Net-(D45-A)") (class "Default")
      (node (ref "D45") (pin "2") (pinfunction "A_2") (pintype "unspecified"))
      (node (ref "SEL2") (pin "3") (pinfunction "C_3") (pintype "unspecified"))
    )
    (net (code "67") (name "Net-(D46-A)") (class "Default")
      (node (ref "D46") (pin "2") (pinfunction "A_2") (pintype "unspecified"))
      (node (ref "SPLIT2") (pin "3") (pinfunction "C_3") (pintype "unspecified"))
    )
    (net (code "68") (name "Net-(FN11-A)") (class "Default")
      (node (ref "FN11") (pin "1") (pinfunction "A_1") (pintype "unspecified"))
      (node (ref "FN12") (pin "2") (pinfunction "B_2") (pintype "unspecified"))
    )
    (net (code "69") (name "Net-(FN12-A)") (class "Default")
      (node (ref "FN12") (pin "1") (pinfunction "A_1") (pintype "unspecified"))
      (node (ref "FN13") (pin "2") (pinfunction "B_2") (pintype "unspecified"))
    )
    (net (code "70") (name "Net-(FN13-A)") (class "Default")
      (node (ref "FN13") (pin "1") (pinfunction "A_1") (pintype "unspecified"))
      (node (ref "FN14") (pin "2") (pinfunction "B_2") (pintype "unspecified"))
    )
    (net (code "71") (name "Net-(FN21-A)") (class "Default")
      (node (ref "FN21") (pin "1") (pinfunction "A_1") (pintype "unspecified"))
      (node (ref "FN22") (pin "2") (pinfunction "B_2") (pintype "unspecified"))
    )
    (net (code "72") (name "Net-(FN22-A)") (class "Default")
      (node (ref "FN22") (pin "1") (pinfunction "A_1") (pintype "unspecified"))
      (node (ref "FN23") (pin "2") (pinfunction "B_2") (pintype "unspecified"))
    )
    (net (code "73") (name "Net-(FN23-A)") (class "Default")
      (node (ref "FN23") (pin "1") (pinfunction "A_1") (pintype "unspecified"))
      (node (ref "FN24") (pin "2") (pinfunction "B_2") (pintype "unspecified"))
    )
    (net (code "74") (name "Net-(FX11-Pad3)") (class "Default")
      (node (ref "FX11") (pin "3") (pinfunction "3_3") (pintype "input"))
      (node (ref "R10") (pin "1") (pinfunction "1_1") (pintype "input"))
    )
    (net (code "75") (name "Net-(FX12-Pad3)") (class "Default")
      (node (ref "FX12") (pin "3") (pinfunction "3_3") (pintype "input"))
      (node (ref "R9") (pin "1") (pinfunction "1_1") (pintype "input"))
    )
    (net (code "76") (name "Net-(FX21-Pad3)") (class "Default")
      (node (ref "FX21") (pin "3") (pinfunction "3_3") (pintype "input"))
      (node (ref "R7") (pin "1") (pinfunction "1_1") (pintype "input"))
    )
    (net (code "77") (name "Net-(FX22-Pad3)") (class "Default")
      (node (ref "FX22") (pin "3") (pinfunction "3_3") (pintype "input"))
      (node (ref "R8") (pin "1") (pinfunction "1_1") (pintype "input"))
    )
    (net (code "78") (name "Net-(LD1-A)") (class "Default")
      (node (ref "LD1") (pin "1") (pinfunction "A_1") (pintype "unspecified"))
      (node (ref "PLAY1") (pin "2") (pinfunction "B_2") (pintype "unspecified"))
    )
    (net (code "79") (name "Net-(LD2-A)") (class "Default")
      (node (ref "LD2") (pin "1") (pinfunction "A_1") (pintype "unspecified"))
      (node (ref "PLAY2") (pin "2") (pinfunction "B_2") (pintype "unspecified"))
    )
    (net (code "80") (name "Net-(PAD11-A)") (class "Default")
      (node (ref "PAD11") (pin "1") (pinfunction "A_1") (pintype "unspecified"))
      (node (ref "PAD13") (pin "2") (pinfunction "B_2") (pintype "unspecified"))
    )
    (net (code "81") (name "Net-(PAD12-A)") (class "Default")
      (node (ref "PAD12") (pin "1") (pinfunction "A_1") (pintype "unspecified"))
      (node (ref "PAD14") (pin "2") (pinfunction "B_2") (pintype "unspecified"))
    )
    (net (code "82") (name "Net-(PAD13-A)") (class "Default")
      (node (ref "PAD13") (pin "1") (pinfunction "A_1") (pintype "unspecified"))
      (node (ref "PAD15") (pin "2") (pinfunction "B_2") (pintype "unspecified"))
    )
    (net (code "83") (name "Net-(PAD14-A)") (class "Default")
      (node (ref "PAD14") (pin "1") (pinfunction "A_1") (pintype "unspecified"))
      (node (ref "PAD16") (pin "2") (pinfunction "B_2") (pintype "unspecified"))
    )
    (net (code "84") (name "Net-(PAD15-A)") (class "Default")
      (node (ref "PAD15") (pin "1") (pinfunction "A_1") (pintype "unspecified"))
      (node (ref "PAD17") (pin "2") (pinfunction "B_2") (pintype "unspecified"))
    )
    (net (code "85") (name "Net-(PAD16-A)") (class "Default")
      (node (ref "PAD16") (pin "1") (pinfunction "A_1") (pintype "unspecified"))
      (node (ref "PAD18") (pin "2") (pinfunction "B_2") (pintype "unspecified"))
    )
    (net (code "86") (name "Net-(PAD21-A)") (class "Default")
      (node (ref "PAD21") (pin "1") (pinfunction "A_1") (pintype "unspecified"))
      (node (ref "PAD23") (pin "2") (pinfunction "B_2") (pintype "unspecified"))
    )
    (net (code "87") (name "Net-(PAD22-A)") (class "Default")
      (node (ref "PAD22") (pin "1") (pinfunction "A_1") (pintype "unspecified"))
      (node (ref "PAD24") (pin "2") (pinfunction "B_2") (pintype "unspecified"))
    )
    (net (code "88") (name "Net-(PAD23-A)") (class "Default")
      (node (ref "PAD23") (pin "1") (pinfunction "A_1") (pintype "unspecified"))
      (node (ref "PAD25") (pin "2") (pinfunction "B_2") (pintype "unspecified"))
    )
    (net (code "89") (name "Net-(PAD24-A)") (class "Default")
      (node (ref "PAD24") (pin "1") (pinfunction "A_1") (pintype "unspecified"))
      (node (ref "PAD26") (pin "2") (pinfunction "B_2") (pintype "unspecified"))
    )
    (net (code "90") (name "Net-(PAD25-A)") (class "Default")
      (node (ref "PAD25") (pin "1") (pinfunction "A_1") (pintype "unspecified"))
      (node (ref "PAD27") (pin "2") (pinfunction "B_2") (pintype "unspecified"))
    )
    (net (code "91") (name "Net-(PAD26-A)") (class "Default")
      (node (ref "PAD26") (pin "1") (pinfunction "A_1") (pintype "unspecified"))
      (node (ref "PAD28") (pin "2") (pinfunction "B_2") (pintype "unspecified"))
    )
    (net (code "92") (name "Net-(PLAY1-A)") (class "Default")
      (node (ref "PLAY1") (pin "1") (pinfunction "A_1") (pintype "unspecified"))
      (node (ref "SEL1") (pin "2") (pinfunction "B_2") (pintype "unspecified"))
    )
    (net (code "93") (name "Net-(PLAY2-A)") (class "Default")
      (node (ref "PLAY2") (pin "1") (pinfunction "A_1") (pintype "unspecified"))
      (node (ref "SEL2") (pin "2") (pinfunction "B_2") (pintype "unspecified"))
    )
    (net (code "94") (name "Net-(R5-Pad1)") (class "Default")
      (node (ref "R5") (pin "1") (pinfunction "1_1") (pintype "input"))
      (node (ref "Tempo2") (pin "3") (pinfunction "3_3") (pintype "input"))
    )
    (net (code "95") (name "Net-(R6-Pad1)") (class "Default")
      (node (ref "R6") (pin "1") (pinfunction "1_1") (pintype "input"))
      (node (ref "Vol2") (pin "3") (pinfunction "3_3") (pintype "input"))
    )
    (net (code "96") (name "Net-(R11-Pad1)") (class "Default")
      (node (ref "R11") (pin "1") (pinfunction "1_1") (pintype "input"))
      (node (ref "Vol1") (pin "3") (pinfunction "3_3") (pintype "input"))
    )
    (net (code "97") (name "Net-(R12-Pad1)") (class "Default")
      (node (ref "R12") (pin "1") (pinfunction "1_1") (pintype "input"))
      (node (ref "Tempo1") (pin "3") (pinfunction "3_3") (pintype "input"))
    )
    (net (code "98") (name "Net-(R13-Pad1)") (class "Default")
      (node (ref "R13") (pin "1") (pinfunction "1_1") (pintype "input"))
      (node (ref "XFader") (pin "3") (pinfunction "3_3") (pintype "input"))
    )
    (net (code "99") (name "Net-(SH1-A)") (class "Default")
      (node (ref "SH1") (pin "1") (pinfunction "A_1") (pintype "unspecified"))
      (node (ref "SH2") (pin "2") (pinfunction "B_2") (pintype "unspecified"))
    )
    (net (code "100") (name "Net-(TSH11-A)") (class "Default")
      (node (ref "TSH11") (pin "1") (pinfunction "A_1") (pintype "unspecified"))
      (node (ref "TSH12") (pin "2") (pinfunction "B_2") (pintype "unspecified"))
    )
    (net (code "101") (name "Net-(TSH12-A)") (class "Default")
      (node (ref "TSH12") (pin "1") (pinfunction "A_1") (pintype "unspecified"))
      (node (ref "TSH13") (pin "2") (pinfunction "B_2") (pintype "unspecified"))
    )
    (net (code "102") (name "Net-(TSH13-A)") (class "Default")
      (node (ref "TSH13") (pin "1") (pinfunction "A_1") (pintype "unspecified"))
      (node (ref "TSH14") (pin "2") (pinfunction "B_2") (pintype "unspecified"))
    )
    (net (code "103") (name "Net-(TSH21-A)") (class "Default")
      (node (ref "TSH21") (pin "1") (pinfunction "A_1") (pintype "unspecified"))
      (node (ref "TSH22") (pin "2") (pinfunction "B_2") (pintype "unspecified"))
    )
    (net (code "104") (name "Net-(TSH22-A)") (class "Default")
      (node (ref "TSH22") (pin "1") (pinfunction "A_1") (pintype "unspecified"))
      (node (ref "TSH23") (pin "2") (pinfunction "B_2") (pintype "unspecified"))
    )
    (net (code "105") (name "Net-(TSH23-A)") (class "Default")
      (node (ref "TSH23") (pin "1") (pinfunction "A_1") (pintype "unspecified"))
      (node (ref "TSH24") (pin "2") (pinfunction "B_2") (pintype "unspecified"))
    )
    (net (code "106") (name "P1") (class "Default")
      (node (ref "D11") (pin "1") (pinfunction "C_1") (pintype "unspecified"))
      (node (ref "D19") (pin "1") (pinfunction "C_1") (pintype "unspecified"))
      (node (ref "D27") (pin "1") (pinfunction "C_1") (pintype "unspecified"))
      (node (ref "D3") (pin "1") (pinfunction "C_1") (pintype "unspecified"))
      (node (ref "D35") (pin "1") (pinfunction "C_1") (pintype "unspecified"))
      (node (ref "D41") (pin "1") (pinfunction "C_1") (pintype "unspecified"))
      (node (ref "U2") (pin "14") (pinfunction "H_14") (pintype "input"))
    )
    (net (code "107") (name "P2") (class "Default")
      (node (ref "D1") (pin "1") (pinfunction "C_1") (pintype "unspecified"))
      (node (ref "D12") (pin "1") (pinfunction "C_1") (pintype "unspecified"))
      (node (ref "D20") (pin "1") (pinfunction "C_1") (pintype "unspecified"))
      (node (ref "D28") (pin "1") (pinfunction "C_1") (pintype "unspecified"))
      (node (ref "D36") (pin "1") (pinfunction "C_1") (pintype "unspecified"))
      (node (ref "D4") (pin "1") (pinfunction "C_1") (pintype "unspecified"))
      (node (ref "D42") (pin "1") (pinfunction "C_1") (pintype "unspecified"))
      (node (ref "U2") (pin "12") (pinfunction "G_12") (pintype "input"))
    )
    (net (code "108") (name "P3") (class "Default")
      (node (ref "D13") (pin "1") (pinfunction "C_1") (pintype "unspecified"))
      (node (ref "D21") (pin "1") (pinfunction "C_1") (pintype "unspecified"))
      (node (ref "D29") (pin "1") (pinfunction "C_1") (pintype "unspecified"))
      (node (ref "D37") (pin "1") (pinfunction "C_1") (pintype "unspecified"))
      (node (ref "D43") (pin "1") (pinfunction "C_1") (pintype "unspecified"))
      (node (ref "D5") (pin "1") (pinfunction "C_1") (pintype "unspecified"))
      (node (ref "U2") (pin "11") (pinfunction "F_11") (pintype "input"))
    )
    (net (code "109") (name "P4") (class "Default")
      (node (ref "D14") (pin "1") (pinfunction "C_1") (pintype "unspecified"))
      (node (ref "D22") (pin "1") (pinfunction "C_1") (pintype "unspecified"))
      (node (ref "D30") (pin "1") (pinfunction "C_1") (pintype "unspecified"))
      (node (ref "D38") (pin "1") (pinfunction "C_1") (pintype "unspecified"))
      (node (ref "D44") (pin "1") (pinfunction "C_1") (pintype "unspecified"))
      (node (ref "D6") (pin "1") (pinfunction "C_1") (pintype "unspecified"))
      (node (ref "U2") (pin "10") (pinfunction "E_10") (pintype "input"))
    )
    (net (code "110") (name "P5") (class "Default")
      (node (ref "D15") (pin "1") (pinfunction "C_1") (pintype "unspecified"))
      (node (ref "D23") (pin "1") (pinfunction "C_1") (pintype "unspecified"))
      (node (ref "D31") (pin "1") (pinfunction "C_1") (pintype "unspecified"))
      (node (ref "D7") (pin "1") (pinfunction "C_1") (pintype "unspecified"))
      (node (ref "R4") (pin "2") (pinfunction "2_2") (pintype "input"))
      (node (ref "U2") (pin "5") (pinfunction "D_5") (pintype "input"))
    )
    (net (code "111") (name "P6") (class "Default")
      (node (ref "D16") (pin "1") (pinfunction "C_1") (pintype "unspecified"))
      (node (ref "D2") (pin "1") (pinfunction "C_1") (pintype "unspecified"))
      (node (ref "D24") (pin "1") (pinfunction "C_1") (pintype "unspecified"))
      (node (ref "D32") (pin "1") (pinfunction "C_1") (pintype "unspecified"))
      (node (ref "D8") (pin "1") (pinfunction "C_1") (pintype "unspecified"))
      (node (ref "R3") (pin "2") (pinfunction "2_2") (pintype "input"))
      (node (ref "U2") (pin "4") (pinfunction "C_4") (pintype "input"))
    )
    (net (code "112") (name "P7") (class "Default")
      (node (ref "D17") (pin "1") (pinfunction "C_1") (pintype "unspecified"))
      (node (ref "D25") (pin "1") (pinfunction "C_1") (pintype "unspecified"))
      (node (ref "D33") (pin "1") (pinfunction "C_1") (pintype "unspecified"))
      (node (ref "D39") (pin "1") (pinfunction "C_1") (pintype "unspecified"))
      (node (ref "D45") (pin "1") (pinfunction "C_1") (pintype "unspecified"))
      (node (ref "D9") (pin "1") (pinfunction "C_1") (pintype "unspecified"))
      (node (ref "R2") (pin "2") (pinfunction "2_2") (pintype "input"))
      (node (ref "U2") (pin "3") (pinfunction "B_3") (pintype "input"))
    )
    (net (code "113") (name "P8") (class "Default")
      (node (ref "D10") (pin "1") (pinfunction "C_1") (pintype "unspecified"))
      (node (ref "D18") (pin "1") (pinfunction "C_1") (pintype "unspecified"))
      (node (ref "D26") (pin "1") (pinfunction "C_1") (pintype "unspecified"))
      (node (ref "D34") (pin "1") (pinfunction "C_1") (pintype "unspecified"))
      (node (ref "D40") (pin "1") (pinfunction "C_1") (pintype "unspecified"))
      (node (ref "D46") (pin "1") (pinfunction "C_1") (pintype "unspecified"))
      (node (ref "R1") (pin "2") (pinfunction "2_2") (pintype "input"))
      (node (ref "U2") (pin "2") (pinfunction "A_2") (pintype "input"))
    )
    (net (code "114") (name "VCC") (class "Default")
      (node (ref "FX11") (pin "1") (pinfunction "1_1") (pintype "input"))
      (node (ref "FX12") (pin "1") (pinfunction "1_1") (pintype "input"))
      (node (ref "FX21") (pin "1") (pinfunction "1_1") (pintype "input"))
      (node (ref "FX22") (pin "1") (pinfunction "1_1") (pintype "input"))
      (node (ref "Tempo1") (pin "1") (pinfunction "1_1") (pintype "input"))
      (node (ref "Tempo2") (pin "1") (pinfunction "1_1") (pintype "input"))
      (node (ref "U2") (pin "16") (pinfunction "VCC_16") (pintype "input"))
      (node (ref "U3") (pin "16") (pinfunction "VCC_16") (pintype "unspecified"))
      (node (ref "U3") (pin "6") (pinfunction "G2_6") (pintype "unspecified"))
      (node (ref "U4") (pin "21") (pinfunction "VCC_21") (pintype "unspecified"))
      (node (ref "Vol1") (pin "1") (pinfunction "1_1") (pintype "input"))
      (node (ref "Vol2") (pin "1") (pinfunction "1_1") (pintype "input"))
      (node (ref "XFader") (pin "1") (pinfunction "1_1") (pintype "input"))
    )
    (net (code "115") (name "Y0") (class "Default")
      (node (ref "SH1") (pin "2") (pinfunction "B_2") (pintype "unspecified"))
      (node (ref "U3") (pin "15") (pinfunction "Y0_15") (pintype "unspecified"))
    )
    (net (code "116") (name "Y2") (class "Default")
      (node (ref "PAD11") (pin "2") (pinfunction "B_2") (pintype "unspecified"))
      (node (ref "PAD12") (pin "2") (pinfunction "B_2") (pintype "unspecified"))
      (node (ref "U3") (pin "13") (pinfunction "Y2_13") (pintype "unspecified"))
    )
    (net (code "117") (name "Y3") (class "Default")
      (node (ref "PAD21") (pin "2") (pinfunction "B_2") (pintype "unspecified"))
      (node (ref "PAD22") (pin "2") (pinfunction "B_2") (pintype "unspecified"))
      (node (ref "U3") (pin "12") (pinfunction "Y3_12") (pintype "unspecified"))
    )
    (net (code "118") (name "Y4") (class "Default")
      (node (ref "FN11") (pin "2") (pinfunction "B_2") (pintype "unspecified"))
      (node (ref "FN21") (pin "2") (pinfunction "B_2") (pintype "unspecified"))
      (node (ref "U3") (pin "11") (pinfunction "Y4_11") (pintype "unspecified"))
    )
    (net (code "119") (name "Y5") (class "Default")
      (node (ref "TSH11") (pin "2") (pinfunction "B_2") (pintype "unspecified"))
      (node (ref "TSH21") (pin "2") (pinfunction "B_2") (pintype "unspecified"))
      (node (ref "U3") (pin "10") (pinfunction "Y5_10") (pintype "unspecified"))
    )
    (net (code "120") (name "Y6") (class "Default")
      (node (ref "LD1") (pin "2") (pinfunction "B_2") (pintype "unspecified"))
      (node (ref "MUTE1") (pin "2") (pinfunction "B_2") (pintype "unspecified"))
      (node (ref "U3") (pin "9") (pinfunction "Y6_9") (pintype "unspecified"))
    )
    (net (code "121") (name "Y7") (class "Default")
      (node (ref "LD2") (pin "2") (pinfunction "B_2") (pintype "unspecified"))
      (node (ref "MUTE2") (pin "2") (pinfunction "B_2") (pintype "unspecified"))
      (node (ref "U3") (pin "7") (pinfunction "Y7_7") (pintype "unspecified"))
    )
    (net (code "122") (name "unconnected-(CUE1-D-Pad4)") (class "Default")
      (node (ref "CUE1") (pin "4") (pinfunction "D_4") (pintype "unspecified"))
    )
    (net (code "123") (name "unconnected-(CUE2-D-Pad4)") (class "Default")
      (node (ref "CUE2") (pin "4") (pinfunction "D_4") (pintype "unspecified"))
    )
    (net (code "124") (name "unconnected-(FN11-D-Pad4)") (class "Default")
      (node (ref "FN11") (pin "4") (pinfunction "D_4") (pintype "unspecified"))
    )
    (net (code "125") (name "unconnected-(FN12-D-Pad4)") (class "Default")
      (node (ref "FN12") (pin "4") (pinfunction "D_4") (pintype "unspecified"))
    )
    (net (code "126") (name "unconnected-(FN13-D-Pad4)") (class "Default")
      (node (ref "FN13") (pin "4") (pinfunction "D_4") (pintype "unspecified"))
    )
    (net (code "127") (name "unconnected-(FN14-A-Pad1)") (class "Default")
      (node (ref "FN14") (pin "1") (pinfunction "A_1") (pintype "unspecified"))
    )
    (net (code "128") (name "unconnected-(FN14-D-Pad4)") (class "Default")
      (node (ref "FN14") (pin "4") (pinfunction "D_4") (pintype "unspecified"))
    )
    (net (code "129") (name "unconnected-(FN21-D-Pad4)") (class "Default")
      (node (ref "FN21") (pin "4") (pinfunction "D_4") (pintype "unspecified"))
    )
    (net (code "130") (name "unconnected-(FN22-D-Pad4)") (class "Default")
      (node (ref "FN22") (pin "4") (pinfunction "D_4") (pintype "unspecified"))
    )
    (net (code "131") (name "unconnected-(FN23-D-Pad4)") (class "Default")
      (node (ref "FN23") (pin "4") (pinfunction "D_4") (pintype "unspecified"))
    )
    (net (code "132") (name "unconnected-(FN24-A-Pad1)") (class "Default")
      (node (ref "FN24") (pin "1") (pinfunction "A_1") (pintype "unspecified"))
    )
    (net (code "133") (name "unconnected-(FN24-D-Pad4)") (class "Default")
      (node (ref "FN24") (pin "4") (pinfunction "D_4") (pintype "unspecified"))
    )
    (net (code "134") (name "unconnected-(LD1-D-Pad4)") (class "Default")
      (node (ref "LD1") (pin "4") (pinfunction "D_4") (pintype "unspecified"))
    )
    (net (code "135") (name "unconnected-(LD2-D-Pad4)") (class "Default")
      (node (ref "LD2") (pin "4") (pinfunction "D_4") (pintype "unspecified"))
    )
    (net (code "136") (name "unconnected-(MUTE1-D-Pad4)") (class "Default")
      (node (ref "MUTE1") (pin "4") (pinfunction "D_4") (pintype "unspecified"))
    )
    (net (code "137") (name "unconnected-(MUTE2-D-Pad4)") (class "Default")
      (node (ref "MUTE2") (pin "4") (pinfunction "D_4") (pintype "unspecified"))
    )
    (net (code "138") (name "unconnected-(PAD11-D-Pad4)") (class "Default")
      (node (ref "PAD11") (pin "4") (pinfunction "D_4") (pintype "unspecified"))
    )
    (net (code "139") (name "unconnected-(PAD12-D-Pad4)") (class "Default")
      (node (ref "PAD12") (pin "4") (pinfunction "D_4") (pintype "unspecified"))
    )
    (net (code "140") (name "unconnected-(PAD13-D-Pad4)") (class "Default")
      (node (ref "PAD13") (pin "4") (pinfunction "D_4") (pintype "unspecified"))
    )
    (net (code "141") (name "unconnected-(PAD14-D-Pad4)") (class "Default")
      (node (ref "PAD14") (pin "4") (pinfunction "D_4") (pintype "unspecified"))
    )
    (net (code "142") (name "unconnected-(PAD15-D-Pad4)") (class "Default")
      (node (ref "PAD15") (pin "4") (pinfunction "D_4") (pintype "unspecified"))
    )
    (net (code "143") (name "unconnected-(PAD16-D-Pad4)") (class "Default")
      (node (ref "PAD16") (pin "4") (pinfunction "D_4") (pintype "unspecified"))
    )
    (net (code "144") (name "unconnected-(PAD17-A-Pad1)") (class "Default")
      (node (ref "PAD17") (pin "1") (pinfunction "A_1") (pintype "unspecified"))
    )
    (net (code "145") (name "unconnected-(PAD17-D-Pad4)") (class "Default")
      (node (ref "PAD17") (pin "4") (pinfunction "D_4") (pintype "unspecified"))
    )
    (net (code "146") (name "unconnected-(PAD18-A-Pad1)") (class "Default")
      (node (ref "PAD18") (pin "1") (pinfunction "A_1") (pintype "unspecified"))
    )
    (net (code "147") (name "unconnected-(PAD18-D-Pad4)") (class "Default")
      (node (ref "PAD18") (pin "4") (pinfunction "D_4") (pintype "unspecified"))
    )
    (net (code "148") (name "unconnected-(PAD21-D-Pad4)") (class "Default")
      (node (ref "PAD21") (pin "4") (pinfunction "D_4") (pintype "unspecified"))
    )
    (net (code "149") (name "unconnected-(PAD22-D-Pad4)") (class "Default")
      (node (ref "PAD22") (pin "4") (pinfunction "D_4") (pintype "unspecified"))
    )
    (net (code "150") (name "unconnected-(PAD23-D-Pad4)") (class "Default")
      (node (ref "PAD23") (pin "4") (pinfunction "D_4") (pintype "unspecified"))
    )
    (net (code "151") (name "unconnected-(PAD24-D-Pad4)") (class "Default")
      (node (ref "PAD24") (pin "4") (pinfunction "D_4") (pintype "unspecified"))
    )
    (net (code "152") (name "unconnected-(PAD25-D-Pad4)") (class "Default")
      (node (ref "PAD25") (pin "4") (pinfunction "D_4") (pintype "unspecified"))
    )
    (net (code "153") (name "unconnected-(PAD26-D-Pad4)") (class "Default")
      (node (ref "PAD26") (pin "4") (pinfunction "D_4") (pintype "unspecified"))
    )
    (net (code "154") (name "unconnected-(PAD27-A-Pad1)") (class "Default")
      (node (ref "PAD27") (pin "1") (pinfunction "A_1") (pintype "unspecified"))
    )
    (net (code "155") (name "unconnected-(PAD27-D-Pad4)") (class "Default")
      (node (ref "PAD27") (pin "4") (pinfunction "D_4") (pintype "unspecified"))
    )
    (net (code "156") (name "unconnected-(PAD28-A-Pad1)") (class "Default")
      (node (ref "PAD28") (pin "1") (pinfunction "A_1") (pintype "unspecified"))
    )
    (net (code "157") (name "unconnected-(PAD28-D-Pad4)") (class "Default")
      (node (ref "PAD28") (pin "4") (pinfunction "D_4") (pintype "unspecified"))
    )
    (net (code "158") (name "unconnected-(PLAY1-D-Pad4)") (class "Default")
      (node (ref "PLAY1") (pin "4") (pinfunction "D_4") (pintype "unspecified"))
    )
    (net (code "159") (name "unconnected-(PLAY2-D-Pad4)") (class "Default")
      (node (ref "PLAY2") (pin "4") (pinfunction "D_4") (pintype "unspecified"))
    )
    (net (code "160") (name "unconnected-(SEL1-A-Pad1)") (class "Default")
      (node (ref "SEL1") (pin "1") (pinfunction "A_1") (pintype "unspecified"))
    )
    (net (code "161") (name "unconnected-(SEL1-D-Pad4)") (class "Default")
      (node (ref "SEL1") (pin "4") (pinfunction "D_4") (pintype "unspecified"))
    )
    (net (code "162") (name "unconnected-(SEL2-A-Pad1)") (class "Default")
      (node (ref "SEL2") (pin "1") (pinfunction "A_1") (pintype "unspecified"))
    )
    (net (code "163") (name "unconnected-(SEL2-D-Pad4)") (class "Default")
      (node (ref "SEL2") (pin "4") (pinfunction "D_4") (pintype "unspecified"))
    )
    (net (code "164") (name "unconnected-(SH1-D-Pad4)") (class "Default")
      (node (ref "SH1") (pin "4") (pinfunction "D_4") (pintype "unspecified"))
    )
    (net (code "165") (name "unconnected-(SH2-A-Pad1)") (class "Default")
      (node (ref "SH2") (pin "1") (pinfunction "A_1") (pintype "unspecified"))
    )
    (net (code "166") (name "unconnected-(SH2-D-Pad4)") (class "Default")
      (node (ref "SH2") (pin "4") (pinfunction "D_4") (pintype "unspecified"))
    )
    (net (code "167") (name "unconnected-(SPLIT1-A-Pad1)") (class "Default")
      (node (ref "SPLIT1") (pin "1") (pinfunction "A_1") (pintype "unspecified"))
    )
    (net (code "168") (name "unconnected-(SPLIT1-D-Pad4)") (class "Default")
      (node (ref "SPLIT1") (pin "4") (pinfunction "D_4") (pintype "unspecified"))
    )
    (net (code "169") (name "unconnected-(SPLIT2-A-Pad1)") (class "Default")
      (node (ref "SPLIT2") (pin "1") (pinfunction "A_1") (pintype "unspecified"))
    )
    (net (code "170") (name "unconnected-(SPLIT2-D-Pad4)") (class "Default")
      (node (ref "SPLIT2") (pin "4") (pinfunction "D_4") (pintype "unspecified"))
    )
    (net (code "171") (name "unconnected-(TSH11-D-Pad4)") (class "Default")
      (node (ref "TSH11") (pin "4") (pinfunction "D_4") (pintype "unspecified"))
    )
    (net (code "172") (name "unconnected-(TSH12-D-Pad4)") (class "Default")
      (node (ref "TSH12") (pin "4") (pinfunction "D_4") (pintype "unspecified"))
    )
    (net (code "173") (name "unconnected-(TSH13-D-Pad4)") (class "Default")
      (node (ref "TSH13") (pin "4") (pinfunction "D_4") (pintype "unspecified"))
    )
    (net (code "174") (name "unconnected-(TSH14-A-Pad1)") (class "Default")
      (node (ref "TSH14") (pin "1") (pinfunction "A_1") (pintype "unspecified"))
    )
    (net (code "175") (name "unconnected-(TSH14-D-Pad4)") (class "Default")
      (node (ref "TSH14") (pin "4") (pinfunction "D_4") (pintype "unspecified"))
    )
    (net (code "176") (name "unconnected-(TSH21-D-Pad4)") (class "Default")
      (node (ref "TSH21") (pin "4") (pinfunction "D_4") (pintype "unspecified"))
    )
    (net (code "177") (name "unconnected-(TSH22-D-Pad4)") (class "Default")
      (node (ref "TSH22") (pin "4") (pinfunction "D_4") (pintype "unspecified"))
    )
    (net (code "178") (name "unconnected-(TSH23-D-Pad4)") (class "Default")
      (node (ref "TSH23") (pin "4") (pinfunction "D_4") (pintype "unspecified"))
    )
    (net (code "179") (name "unconnected-(TSH24-A-Pad1)") (class "Default")
      (node (ref "TSH24") (pin "1") (pinfunction "A_1") (pintype "unspecified"))
    )
    (net (code "180") (name "unconnected-(TSH24-D-Pad4)") (class "Default")
      (node (ref "TSH24") (pin "4") (pinfunction "D_4") (pintype "unspecified"))
    )
    (net (code "181") (name "unconnected-(U3-Y1-Pad14)") (class "Default")
      (node (ref "U3") (pin "14") (pinfunction "Y1_14") (pintype "unspecified"))
    )
    (net (code "182") (name "unconnected-(U4-GND@1-Pad3)") (class "Default")
      (node (ref "U4") (pin "3") (pinfunction "GND@1_3") (pintype "unspecified"))
    )
    (net (code "183") (name "unconnected-(U4-GND@2-Pad23)") (class "Default")
      (node (ref "U4") (pin "23") (pinfunction "GND@2_23") (pintype "unspecified"))
    )
    (net (code "184") (name "unconnected-(U4-RAW-Pad24)") (class "Default")
      (node (ref "U4") (pin "24") (pinfunction "RAW_24") (pintype "unspecified"))
    )
    (net (code "185") (name "unconnected-(U4-RESET-Pad22)") (class "Default")
      (node (ref "U4") (pin "22") (pinfunction "RESET_22") (pintype "bidirectional"))
    )
    (net (code "186") (name "unconnected-(U4-RXI-Pad2)") (class "Default")
      (node (ref "U4") (pin "2") (pinfunction "RXI_2") (pintype "bidirectional"))
    )
    (net (code "187") (name "unconnected-(U4-TXO-Pad1)") (class "Default")
      (node (ref "U4") (pin "1") (pinfunction "TXO_1") (pintype "bidirectional"))
    )
  )
)
